# Sheet1.net
KiCad netlist of a schematic drawn in Altium Designer
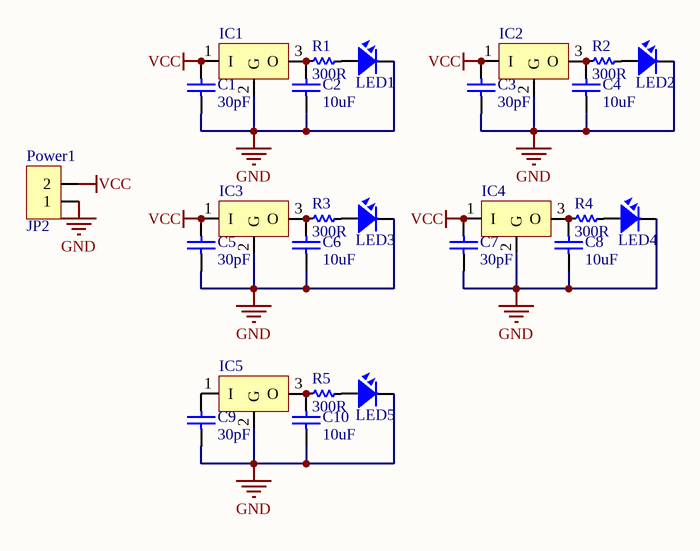
[diagram p0: Sheet1.SchDoc]

(export (version "E")
  (design (tool "Eeschema 10.0.6"))
  (components
    (comp (ref "C1")
      (value "30pF")
      (footprint "C-NP-0805")
      (description "Non-polarized Capacitor")
      (fields (field (name "Comment") "Cap Non-pol") (field (name "PUBLISHER") "Altium Limited"))
      (libsource (lib "hphonglib") (part "Cap Non-pol"))
    )
    (comp (ref "C2")
      (value "10uF")
      (footprint "C-NP-0805")
      (description "Non-polarized Capacitor")
      (fields (field (name "Comment") "Cap Non-pol") (field (name "PUBLISHER") "Altium Limited"))
      (libsource (lib "hphonglib") (part "Cap Non-pol"))
    )
    (comp (ref "C3")
      (value "30pF")
      (footprint "C-NP-0805")
      (description "Non-polarized Capacitor")
      (fields (field (name "Comment") "Cap Non-pol") (field (name "PUBLISHER") "Altium Limited"))
      (libsource (lib "hphonglib") (part "Cap Non-pol"))
    )
    (comp (ref "C4")
      (value "10uF")
      (footprint "C-NP-0805")
      (description "Non-polarized Capacitor")
      (fields (field (name "Comment") "Cap Non-pol") (field (name "PUBLISHER") "Altium Limited"))
      (libsource (lib "hphonglib") (part "Cap Non-pol"))
    )
    (comp (ref "C5")
      (value "30pF")
      (footprint "C-NP-0805")
      (description "Non-polarized Capacitor")
      (fields (field (name "Comment") "Cap Non-pol") (field (name "PUBLISHER") "Altium Limited"))
      (libsource (lib "hphonglib") (part "Cap Non-pol"))
    )
    (comp (ref "C6")
      (value "10uF")
      (footprint "C-NP-0805")
      (description "Non-polarized Capacitor")
      (fields (field (name "Comment") "Cap Non-pol") (field (name "PUBLISHER") "Altium Limited"))
      (libsource (lib "hphonglib") (part "Cap Non-pol"))
    )
    (comp (ref "C7")
      (value "30pF")
      (footprint "C-NP-0805")
      (description "Non-polarized Capacitor")
      (fields (field (name "Comment") "Cap Non-pol") (field (name "PUBLISHER") "Altium Limited"))
      (libsource (lib "hphonglib") (part "Cap Non-pol"))
    )
    (comp (ref "C8")
      (value "10uF")
      (footprint "C-NP-0805")
      (description "Non-polarized Capacitor")
      (fields (field (name "Comment") "Cap Non-pol") (field (name "PUBLISHER") "Altium Limited"))
      (libsource (lib "hphonglib") (part "Cap Non-pol"))
    )
    (comp (ref "C9")
      (value "30pF")
      (footprint "C-NP-0805")
      (description "Non-polarized Capacitor")
      (fields (field (name "Comment") "Cap Non-pol") (field (name "PUBLISHER") "Altium Limited"))
      (libsource (lib "hphonglib") (part "Cap Non-pol"))
    )
    (comp (ref "C10")
      (value "10uF")
      (footprint "C-NP-0805")
      (description "Non-polarized Capacitor")
      (fields (field (name "Comment") "Cap Non-pol") (field (name "PUBLISHER") "Altium Limited"))
      (libsource (lib "hphonglib") (part "Cap Non-pol"))
    )
    (comp (ref "IC1")
      (value "LM78xx")
      (footprint "TO252-123")
      (description "Positive Voltage Regulator")
      (fields (field (name "PUBLISHER") "Altium Limited"))
      (libsource (lib "LIBRARY") (part "LM78xx"))
    )
    (comp (ref "IC2")
      (value "LM78xx")
      (footprint "TO252-123")
      (description "Positive Voltage Regulator")
      (fields (field (name "PUBLISHER") "Altium Limited"))
      (libsource (lib "LIBRARY") (part "LM78xx"))
    )
    (comp (ref "IC3")
      (value "LM78xx")
      (footprint "TO252-123")
      (description "Positive Voltage Regulator")
      (fields (field (name "PUBLISHER") "Altium Limited"))
      (libsource (lib "LIBRARY") (part "LM78xx"))
    )
    (comp (ref "IC4")
      (value "LM78xx")
      (footprint "TO252-123")
      (description "Positive Voltage Regulator")
      (fields (field (name "PUBLISHER") "Altium Limited"))
      (libsource (lib "LIBRARY") (part "LM78xx"))
    )
    (comp (ref "IC5")
      (value "LM78xx")
      (footprint "TO252-123")
      (description "Positive Voltage Regulator")
      (fields (field (name "PUBLISHER") "Altium Limited"))
      (libsource (lib "LIBRARY") (part "LM78xx"))
    )
    (comp (ref "LED1") (value "LED") (footprint "LED-1206-Blue") (libsource (lib "LIBRARY") (part "LED SMD")))
    (comp (ref "LED2") (value "LED") (footprint "LED-1206-Blue") (libsource (lib "LIBRARY") (part "LED SMD")))
    (comp (ref "LED3") (value "LED") (footprint "LED-1206-Blue") (libsource (lib "LIBRARY") (part "LED SMD")))
    (comp (ref "LED4") (value "LED") (footprint "LED-1206-Blue") (libsource (lib "LIBRARY") (part "LED SMD")))
    (comp (ref "LED5") (value "LED") (footprint "LED-1206-Blue") (libsource (lib "LIBRARY") (part "LED SMD")))
    (comp (ref "Power1")
      (value "JP2")
      (footprint "JP2-D1T")
      (description "WR-PHD 2.54 mm Angled Socket Header")
      (fields
        (field (name "MANUFACTURER") "Würth Elektronik eiSos GmbH")
        (field (name "PARTNO") "613002143121")
        (field (name "CREATED BY") "Karrer Zheng")
      )
      (libsource (lib "LIBRARY") (part "JP2"))
    )
    (comp (ref "R1")
      (value "300R")
      (footprint "RES-SMD-1206")
      (description "Resistor")
      (fields
        (field (name "MANUFACTURER") "Generic Components")
        (field (name "PUBLISHER") "Altium Hobart Technology Centre")
      )
      (libsource (lib "LIBRARY") (part "Res-SMD"))
    )
    (comp (ref "R2")
      (value "300R")
      (footprint "RES-SMD-1206")
      (description "Resistor")
      (fields
        (field (name "MANUFACTURER") "Generic Components")
        (field (name "PUBLISHER") "Altium Hobart Technology Centre")
      )
      (libsource (lib "LIBRARY") (part "Res-SMD"))
    )
    (comp (ref "R3")
      (value "300R")
      (footprint "RES-SMD-1206")
      (description "Resistor")
      (fields
        (field (name "MANUFACTURER") "Generic Components")
        (field (name "PUBLISHER") "Altium Hobart Technology Centre")
      )
      (libsource (lib "LIBRARY") (part "Res-SMD"))
    )
    (comp (ref "R4")
      (value "300R")
      (footprint "RES-SMD-1206")
      (description "Resistor")
      (fields
        (field (name "MANUFACTURER") "Generic Components")
        (field (name "PUBLISHER") "Altium Hobart Technology Centre")
      )
      (libsource (lib "LIBRARY") (part "Res-SMD"))
    )
    (comp (ref "R5")
      (value "300R")
      (footprint "RES-SMD-1206")
      (description "Resistor")
      (fields
        (field (name "MANUFACTURER") "Generic Components")
        (field (name "PUBLISHER") "Altium Hobart Technology Centre")
      )
      (libsource (lib "LIBRARY") (part "Res-SMD"))
    )
  )
  (nets
    (net (code "1") (name "GND") (class "Default")
      (node (ref "C1") (pin "2") (pinfunction "2_2") (pintype "passive"))
      (node (ref "C10") (pin "2") (pinfunction "2_2") (pintype "passive"))
      (node (ref "C2") (pin "2") (pinfunction "2_2") (pintype "passive"))
      (node (ref "C3") (pin "2") (pinfunction "2_2") (pintype "passive"))
      (node (ref "C4") (pin "2") (pinfunction "2_2") (pintype "passive"))
      (node (ref "C5") (pin "2") (pinfunction "2_2") (pintype "passive"))
      (node (ref "C6") (pin "2") (pinfunction "2_2") (pintype "passive"))
      (node (ref "C7") (pin "2") (pinfunction "2_2") (pintype "passive"))
      (node (ref "C8") (pin "2") (pinfunction "2_2") (pintype "passive"))
      (node (ref "C9") (pin "2") (pinfunction "2_2") (pintype "passive"))
      (node (ref "IC1") (pin "2") (pinfunction "G_2") (pintype "power_in"))
      (node (ref "IC2") (pin "2") (pinfunction "G_2") (pintype "power_in"))
      (node (ref "IC3") (pin "2") (pinfunction "G_2") (pintype "power_in"))
      (node (ref "IC4") (pin "2") (pinfunction "G_2") (pintype "power_in"))
      (node (ref "IC5") (pin "2") (pinfunction "G_2") (pintype "power_in"))
      (node (ref "LED1") (pin "2") (pinfunction "2_2") (pintype "passive"))
      (node (ref "LED2") (pin "2") (pinfunction "2_2") (pintype "passive"))
      (node (ref "LED3") (pin "2") (pinfunction "2_2") (pintype "passive"))
      (node (ref "LED4") (pin "2") (pinfunction "2_2") (pintype "passive"))
      (node (ref "LED5") (pin "2") (pinfunction "2_2") (pintype "passive"))
      (node (ref "Power1") (pin "1") (pinfunction "1_1") (pintype "passive"))
    )
    (net (code "2") (name "Net-(IC1-O)") (class "Default")
      (node (ref "C2") (pin "1") (pinfunction "1_1") (pintype "passive"))
      (node (ref "IC1") (pin "3") (pinfunction "O_3") (pintype "power_in"))
      (node (ref "R1") (pin "1") (pinfunction "1_1") (pintype "passive"))
    )
    (net (code "3") (name "Net-(IC2-O)") (class "Default")
      (node (ref "C4") (pin "1") (pinfunction "1_1") (pintype "passive"))
      (node (ref "IC2") (pin "3") (pinfunction "O_3") (pintype "power_in"))
      (node (ref "R2") (pin "1") (pinfunction "1_1") (pintype "passive"))
    )
    (net (code "4") (name "Net-(IC3-O)") (class "Default")
      (node (ref "C6") (pin "1") (pinfunction "1_1") (pintype "passive"))
      (node (ref "IC3") (pin "3") (pinfunction "O_3") (pintype "power_in"))
      (node (ref "R3") (pin "1") (pinfunction "1_1") (pintype "passive"))
    )
    (net (code "5") (name "Net-(IC4-O)") (class "Default")
      (node (ref "C8") (pin "1") (pinfunction "1_1") (pintype "passive"))
      (node (ref "IC4") (pin "3") (pinfunction "O_3") (pintype "power_in"))
      (node (ref "R4") (pin "1") (pinfunction "1_1") (pintype "passive"))
    )
    (net (code "6") (name "Net-(IC5-I)") (class "Default")
      (node (ref "C9") (pin "1") (pinfunction "1_1") (pintype "passive"))
      (node (ref "IC5") (pin "1") (pinfunction "I_1") (pintype "power_in"))
    )
    (net (code "7") (name "Net-(IC5-O)") (class "Default")
      (node (ref "C10") (pin "1") (pinfunction "1_1") (pintype "passive"))
      (node (ref "IC5") (pin "3") (pinfunction "O_3") (pintype "power_in"))
      (node (ref "R5") (pin "1") (pinfunction "1_1") (pintype "passive"))
    )
    (net (code "8") (name "Net-(LED1-Pad1)") (class "Default")
      (node (ref "LED1") (pin "1") (pinfunction "1_1") (pintype "passive"))
      (node (ref "R1") (pin "2") (pinfunction "2_2") (pintype "passive"))
    )
    (net (code "9") (name "Net-(LED2-Pad1)") (class "Default")
      (node (ref "LED2") (pin "1") (pinfunction "1_1") (pintype "passive"))
      (node (ref "R2") (pin "2") (pinfunction "2_2") (pintype "passive"))
    )
    (net (code "10") (name "Net-(LED3-Pad1)") (class "Default")
      (node (ref "LED3") (pin "1") (pinfunction "1_1") (pintype "passive"))
      (node (ref "R3") (pin "2") (pinfunction "2_2") (pintype "passive"))
    )
    (net (code "11") (name "Net-(LED4-Pad1)") (class "Default")
      (node (ref "LED4") (pin "1") (pinfunction "1_1") (pintype "passive"))
      (node (ref "R4") (pin "2") (pinfunction "2_2") (pintype "passive"))
    )
    (net (code "12") (name "Net-(LED5-Pad1)") (class "Default")
      (node (ref "LED5") (pin "1") (pinfunction "1_1") (pintype "passive"))
      (node (ref "R5") (pin "2") (pinfunction "2_2") (pintype "passive"))
    )
    (net (code "13") (name "VCC") (class "Default")
      (node (ref "C1") (pin "1") (pinfunction "1_1") (pintype "passive"))
      (node (ref "C3") (pin "1") (pinfunction "1_1") (pintype "passive"))
      (node (ref "C5") (pin "1") (pinfunction "1_1") (pintype "passive"))
      (node (ref "C7") (pin "1") (pinfunction "1_1") (pintype "passive"))
      (node (ref "IC1") (pin "1") (pinfunction "I_1") (pintype "power_in"))
      (node (ref "IC2") (pin "1") (pinfunction "I_1") (pintype "power_in"))
      (node (ref "IC3") (pin "1") (pinfunction "I_1") (pintype "power_in"))
      (node (ref "IC4") (pin "1") (pinfunction "I_1") (pintype "power_in"))
      (node (ref "Power1") (pin "2") (pinfunction "2_2") (pintype "passive"))
    )
  )
)
